# daughterboard.net
KiCad netlist of a schematic drawn in EAGLE
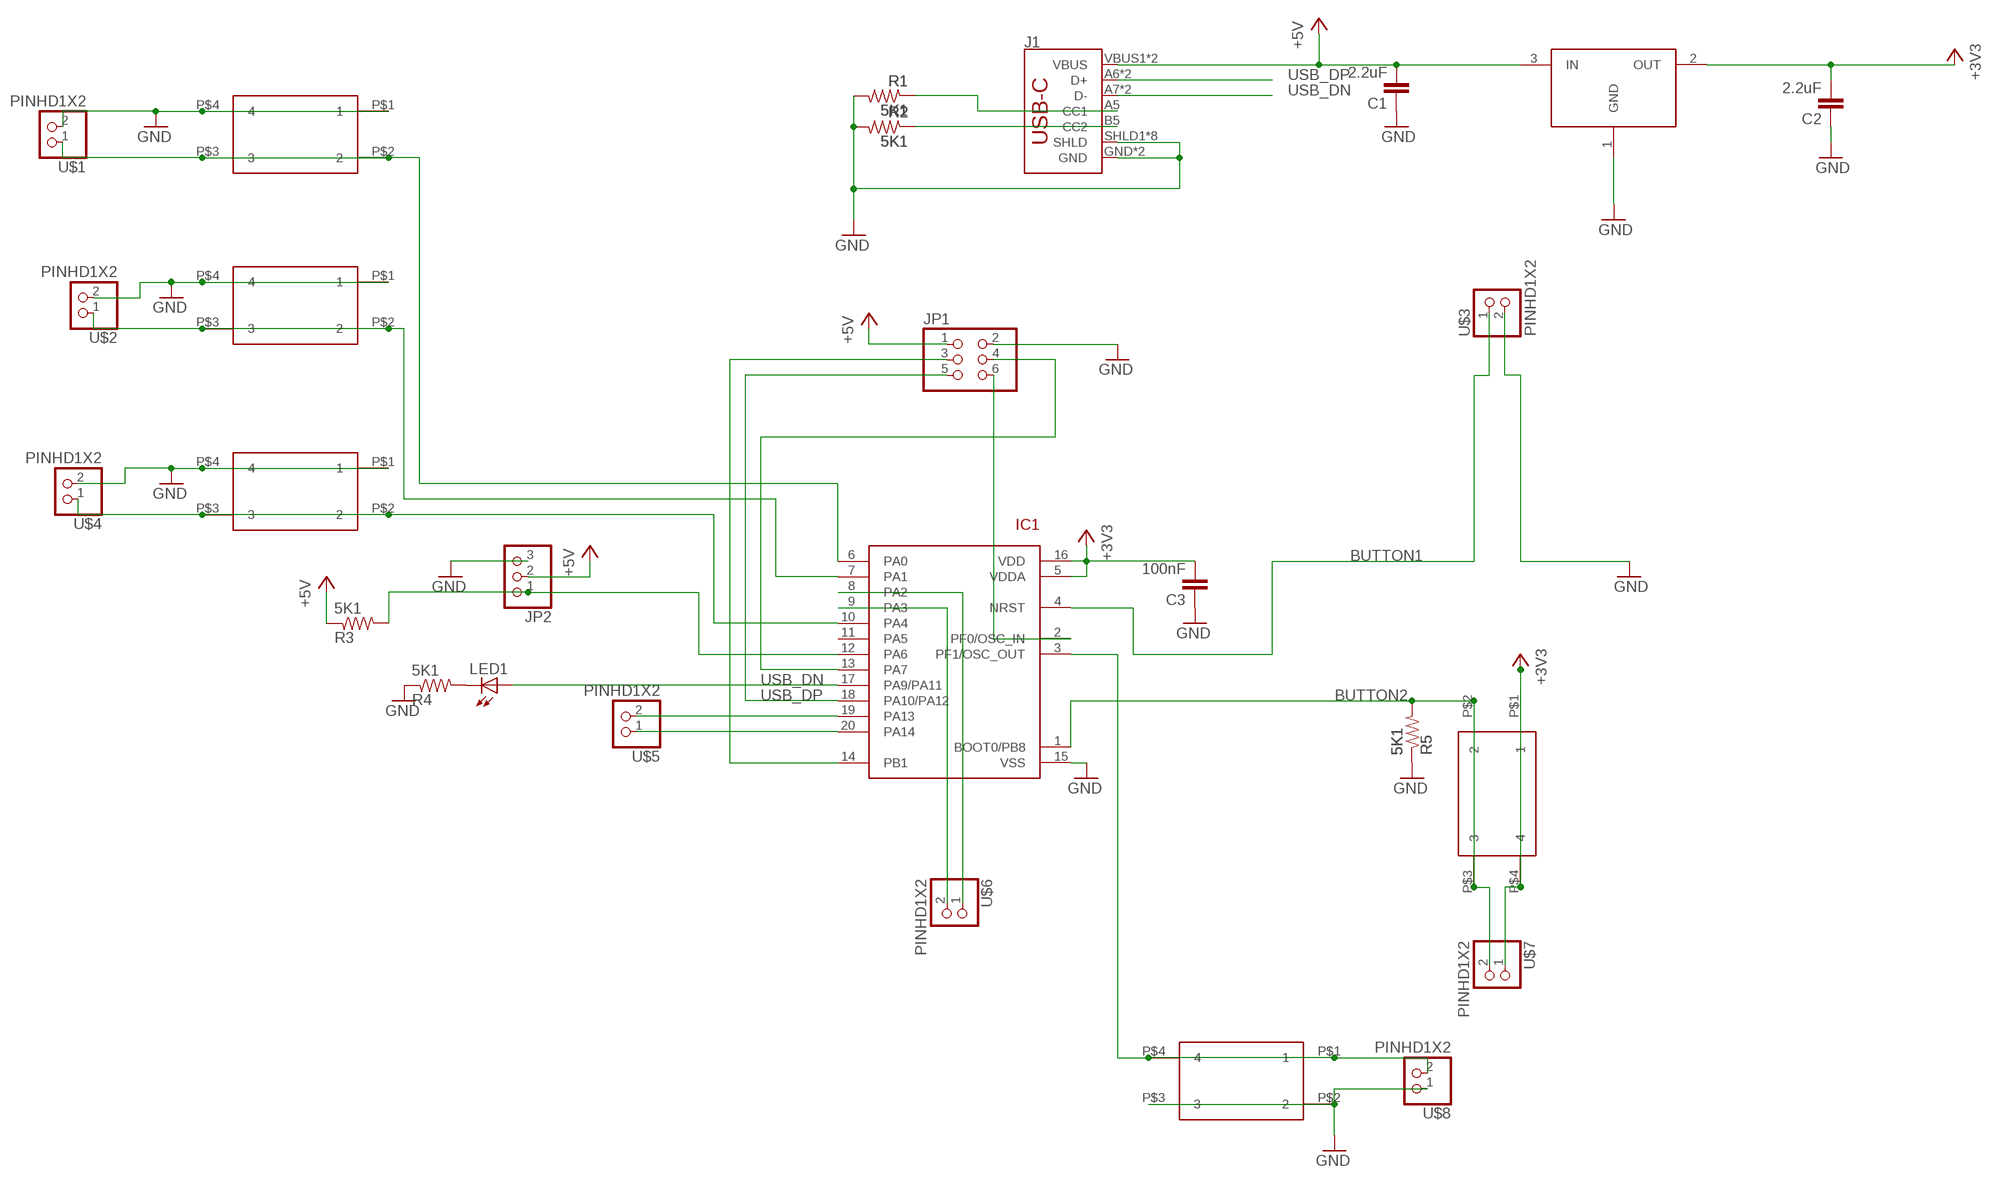
[diagram p0: schematic, sheet 1]

(export (version "E")
  (design (tool "Eeschema 10.0.6"))
  (components
    (comp (ref "C1")
      (value "2.2uF")
      (footprint "eagle-import:0805@1")
      (libsource (lib "eagle-import") (part "CAP0805"))
    )
    (comp (ref "C2")
      (value "2.2uF")
      (footprint "eagle-import:0805@1")
      (libsource (lib "eagle-import") (part "CAP0805"))
    )
    (comp (ref "C3")
      (value "100nF")
      (footprint "eagle-import:0805@1")
      (libsource (lib "eagle-import") (part "CAP0805"))
    )
    (comp (ref "IC1")
      (value "STM32F042F4")
      (footprint "eagle-import:TSSOP20")
      (libsource (lib "eagle-import") (part "STM32F042F4"))
    )
    (comp (ref "J1")
      (value "USB_C16PIN")
      (footprint "eagle-import:USB-C-16P")
      (libsource (lib "eagle-import") (part "USB_C16PIN"))
    )
    (comp (ref "JP1")
      (value "PINHD-2X3")
      (footprint "eagle-import:2X03")
      (libsource (lib "eagle-import") (part "PINHD-2X3"))
    )
    (comp (ref "JP2")
      (value "PINHD-1X3CB")
      (footprint "eagle-import:1X03-CLEANBIG")
      (libsource (lib "eagle-import") (part "PINHD-1X3CB"))
    )
    (comp (ref "LED1")
      (value "LEDCHIP-LED0805")
      (footprint "eagle-import:CHIP-LED0805")
      (libsource (lib "eagle-import") (part "LEDCHIP-LED0805"))
    )
    (comp (ref "R1")
      (value "5K1")
      (footprint "eagle-import:0805")
      (libsource (lib "eagle-import") (part "joyAnalog_RESISTOR0805-RES"))
    )
    (comp (ref "R2")
      (value "5K1")
      (footprint "eagle-import:0805")
      (libsource (lib "eagle-import") (part "joyAnalog_RESISTOR0805-RES"))
    )
    (comp (ref "R3")
      (value "5K1")
      (footprint "eagle-import:0805")
      (libsource (lib "eagle-import") (part "RESISTOR0805-RES"))
    )
    (comp (ref "R4")
      (value "5K1")
      (footprint "eagle-import:0805")
      (libsource (lib "eagle-import") (part "RESISTOR0805-RES"))
    )
    (comp (ref "R5")
      (value "5K1")
      (footprint "eagle-import:0805")
      (libsource (lib "eagle-import") (part "joyAnalog_RESISTOR0805-RES"))
    )
    (comp (ref "SW1")
      (value "324_SW")
      (footprint "eagle-import:342_SWICH_FOOT")
      (libsource (lib "eagle-import") (part "324_SW"))
    )
    (comp (ref "SW2")
      (value "324_SW")
      (footprint "eagle-import:342_SWICH_FOOT")
      (libsource (lib "eagle-import") (part "324_SW"))
    )
    (comp (ref "SW3")
      (value "324_SW")
      (footprint "eagle-import:342_SWICH_FOOT")
      (libsource (lib "eagle-import") (part "324_SW"))
    )
    (comp (ref "SW4")
      (value "324_SW")
      (footprint "eagle-import:342_SWICH_FOOT")
      (libsource (lib "eagle-import") (part "324_SW"))
    )
    (comp (ref "SW5")
      (value "324_SW")
      (footprint "eagle-import:342_SWICH_FOOT")
      (libsource (lib "eagle-import") (part "324_SW"))
    )
    (comp (ref "U$1")
      (value "PINHD1X2")
      (footprint "eagle-import:1X02")
      (libsource (lib "eagle-import") (part "PINHD1X2"))
    )
    (comp (ref "U$2")
      (value "PINHD1X2")
      (footprint "eagle-import:1X02")
      (libsource (lib "eagle-import") (part "PINHD1X2"))
    )
    (comp (ref "U$3")
      (value "PINHD1X2")
      (footprint "eagle-import:1X02")
      (libsource (lib "eagle-import") (part "PINHD1X2"))
    )
    (comp (ref "U$4")
      (value "PINHD1X2")
      (footprint "eagle-import:1X02")
      (libsource (lib "eagle-import") (part "PINHD1X2"))
    )
    (comp (ref "U$5")
      (value "PINHD1X2")
      (footprint "eagle-import:1X02")
      (libsource (lib "eagle-import") (part "PINHD1X2"))
    )
    (comp (ref "U$6")
      (value "PINHD1X2")
      (footprint "eagle-import:1X02")
      (libsource (lib "eagle-import") (part "PINHD1X2"))
    )
    (comp (ref "U$7")
      (value "PINHD1X2")
      (footprint "eagle-import:1X02")
      (libsource (lib "eagle-import") (part "PINHD1X2"))
    )
    (comp (ref "U$8")
      (value "PINHD1X2")
      (footprint "eagle-import:1X02")
      (libsource (lib "eagle-import") (part "PINHD1X2"))
    )
    (comp (ref "U1")
      (value "XC6206_DEV")
      (footprint "eagle-import:SOT23R_INFINEON")
      (libsource (lib "eagle-import") (part "XC6206_DEV"))
    )
  )
  (nets
    (net (code "1") (name "+3V3") (class "Default")
      (node (ref "C2") (pin "2") (pinfunction "2_2") (pintype "passive"))
      (node (ref "C3") (pin "2") (pinfunction "2_2") (pintype "passive"))
      (node (ref "IC1") (pin "16") (pinfunction "VDD_16") (pintype "bidirectional"))
      (node (ref "IC1") (pin "5") (pinfunction "VDDA_5") (pintype "bidirectional"))
      (node (ref "SW4") (pin "P$1") (pinfunction "1_P$1") (pintype "bidirectional"))
      (node (ref "SW4") (pin "P$4") (pinfunction "4_P$4") (pintype "bidirectional"))
      (node (ref "U$7") (pin "1") (pinfunction "1_1") (pintype "passive"))
      (node (ref "U1") (pin "2") (pinfunction "OUT_2") (pintype "bidirectional"))
    )
    (net (code "2") (name "+5V") (class "Default")
      (node (ref "C1") (pin "2") (pinfunction "2_2") (pintype "passive"))
      (node (ref "J1") (pin "VBUS1") (pinfunction "VBUS_VBUS1") (pintype "bidirectional"))
      (node (ref "J1") (pin "VBUS2") (pinfunction "VBUS_VBUS2") (pintype "bidirectional"))
      (node (ref "JP1") (pin "1") (pinfunction "1_1") (pintype "passive"))
      (node (ref "JP2") (pin "2") (pinfunction "2_2") (pintype "passive"))
      (node (ref "R3") (pin "1") (pinfunction "1_1") (pintype "passive"))
      (node (ref "U1") (pin "3") (pinfunction "IN_3") (pintype "bidirectional"))
    )
    (net (code "3") (name "/BUTTON1") (class "Default")
      (node (ref "IC1") (pin "4") (pinfunction "NRST_4") (pintype "bidirectional"))
      (node (ref "U$3") (pin "1") (pinfunction "1_1") (pintype "passive"))
    )
    (net (code "4") (name "/BUTTON2") (class "Default")
      (node (ref "IC1") (pin "1") (pinfunction "BOOT0/PB8_1") (pintype "bidirectional"))
      (node (ref "R5") (pin "2") (pinfunction "2_2") (pintype "passive"))
      (node (ref "SW4") (pin "P$2") (pinfunction "2_P$2") (pintype "bidirectional"))
      (node (ref "SW4") (pin "P$3") (pinfunction "3_P$3") (pintype "bidirectional"))
      (node (ref "U$7") (pin "2") (pinfunction "2_2") (pintype "passive"))
    )
    (net (code "5") (name "/USB_DN") (class "Default")
      (node (ref "IC1") (pin "17") (pinfunction "PA9/PA11_17") (pintype "bidirectional"))
      (node (ref "J1") (pin "A7") (pinfunction "D-_A7") (pintype "bidirectional"))
      (node (ref "J1") (pin "B7") (pinfunction "D-_B7") (pintype "bidirectional"))
      (node (ref "LED1") (pin "A") (pinfunction "A_A") (pintype "passive"))
    )
    (net (code "6") (name "/USB_DP") (class "Default")
      (node (ref "IC1") (pin "18") (pinfunction "PA10/PA12_18") (pintype "bidirectional"))
      (node (ref "J1") (pin "A6") (pinfunction "D+_A6") (pintype "bidirectional"))
      (node (ref "J1") (pin "B6") (pinfunction "D+_B6") (pintype "bidirectional"))
      (node (ref "JP1") (pin "5") (pinfunction "5_5") (pintype "passive"))
    )
    (net (code "7") (name "GND") (class "Default")
      (node (ref "C1") (pin "1") (pinfunction "1_1") (pintype "passive"))
      (node (ref "C2") (pin "1") (pinfunction "1_1") (pintype "passive"))
      (node (ref "C3") (pin "1") (pinfunction "1_1") (pintype "passive"))
      (node (ref "IC1") (pin "15") (pinfunction "VSS_15") (pintype "bidirectional"))
      (node (ref "J1") (pin "GND") (pinfunction "GND_GND") (pintype "bidirectional"))
      (node (ref "J1") (pin "GND2") (pinfunction "GND_GND2") (pintype "bidirectional"))
      (node (ref "J1") (pin "SHLD1") (pinfunction "SHLD_SHLD1") (pintype "bidirectional"))
      (node (ref "J1") (pin "SHLD2") (pinfunction "SHLD_SHLD2") (pintype "bidirectional"))
      (node (ref "J1") (pin "SHLD3") (pinfunction "SHLD_SHLD3") (pintype "bidirectional"))
      (node (ref "J1") (pin "SHLD4") (pinfunction "SHLD_SHLD4") (pintype "bidirectional"))
      (node (ref "J1") (pin "SHLD5") (pinfunction "SHLD_SHLD5") (pintype "bidirectional"))
      (node (ref "J1") (pin "SHLD6") (pinfunction "SHLD_SHLD6") (pintype "bidirectional"))
      (node (ref "J1") (pin "SHLD7") (pinfunction "SHLD_SHLD7") (pintype "bidirectional"))
      (node (ref "J1") (pin "SHLD8") (pinfunction "SHLD_SHLD8") (pintype "bidirectional"))
      (node (ref "JP1") (pin "2") (pinfunction "2_2") (pintype "passive"))
      (node (ref "JP2") (pin "3") (pinfunction "3_3") (pintype "passive"))
      (node (ref "R1") (pin "2") (pinfunction "2_2") (pintype "passive"))
      (node (ref "R2") (pin "2") (pinfunction "2_2") (pintype "passive"))
      (node (ref "R4") (pin "1") (pinfunction "1_1") (pintype "passive"))
      (node (ref "R5") (pin "1") (pinfunction "1_1") (pintype "passive"))
      (node (ref "SW1") (pin "P$1") (pinfunction "1_P$1") (pintype "bidirectional"))
      (node (ref "SW1") (pin "P$4") (pinfunction "4_P$4") (pintype "bidirectional"))
      (node (ref "SW2") (pin "P$1") (pinfunction "1_P$1") (pintype "bidirectional"))
      (node (ref "SW2") (pin "P$4") (pinfunction "4_P$4") (pintype "bidirectional"))
      (node (ref "SW3") (pin "P$1") (pinfunction "1_P$1") (pintype "bidirectional"))
      (node (ref "SW3") (pin "P$4") (pinfunction "4_P$4") (pintype "bidirectional"))
      (node (ref "SW5") (pin "P$2") (pinfunction "2_P$2") (pintype "bidirectional"))
      (node (ref "SW5") (pin "P$3") (pinfunction "3_P$3") (pintype "bidirectional"))
      (node (ref "U$1") (pin "2") (pinfunction "2_2") (pintype "passive"))
      (node (ref "U$2") (pin "2") (pinfunction "2_2") (pintype "passive"))
      (node (ref "U$3") (pin "2") (pinfunction "2_2") (pintype "passive"))
      (node (ref "U$4") (pin "2") (pinfunction "2_2") (pintype "passive"))
      (node (ref "U$8") (pin "1") (pinfunction "1_1") (pintype "passive"))
      (node (ref "U1") (pin "1") (pinfunction "GND_1") (pintype "bidirectional"))
    )
    (net (code "8") (name "Net-(IC1-PA0)") (class "Default")
      (node (ref "IC1") (pin "6") (pinfunction "PA0_6") (pintype "bidirectional"))
      (node (ref "SW1") (pin "P$2") (pinfunction "2_P$2") (pintype "bidirectional"))
      (node (ref "SW1") (pin "P$3") (pinfunction "3_P$3") (pintype "bidirectional"))
      (node (ref "U$1") (pin "1") (pinfunction "1_1") (pintype "passive"))
    )
    (net (code "9") (name "Net-(IC1-PA1)") (class "Default")
      (node (ref "IC1") (pin "7") (pinfunction "PA1_7") (pintype "bidirectional"))
      (node (ref "SW2") (pin "P$2") (pinfunction "2_P$2") (pintype "bidirectional"))
      (node (ref "SW2") (pin "P$3") (pinfunction "3_P$3") (pintype "bidirectional"))
      (node (ref "U$2") (pin "1") (pinfunction "1_1") (pintype "passive"))
    )
    (net (code "10") (name "Net-(IC1-PA2)") (class "Default")
      (node (ref "IC1") (pin "8") (pinfunction "PA2_8") (pintype "bidirectional"))
      (node (ref "U$6") (pin "1") (pinfunction "1_1") (pintype "passive"))
    )
    (net (code "11") (name "Net-(IC1-PA3)") (class "Default")
      (node (ref "IC1") (pin "9") (pinfunction "PA3_9") (pintype "bidirectional"))
      (node (ref "U$6") (pin "2") (pinfunction "2_2") (pintype "passive"))
    )
    (net (code "12") (name "Net-(IC1-PA4)") (class "Default")
      (node (ref "IC1") (pin "10") (pinfunction "PA4_10") (pintype "bidirectional"))
      (node (ref "SW3") (pin "P$2") (pinfunction "2_P$2") (pintype "bidirectional"))
      (node (ref "SW3") (pin "P$3") (pinfunction "3_P$3") (pintype "bidirectional"))
      (node (ref "U$4") (pin "1") (pinfunction "1_1") (pintype "passive"))
    )
    (net (code "13") (name "Net-(IC1-PA6)") (class "Default")
      (node (ref "IC1") (pin "12") (pinfunction "PA6_12") (pintype "bidirectional"))
      (node (ref "JP2") (pin "1") (pinfunction "1_1") (pintype "passive"))
      (node (ref "R3") (pin "2") (pinfunction "2_2") (pintype "passive"))
    )
    (net (code "14") (name "Net-(IC1-PA7)") (class "Default")
      (node (ref "IC1") (pin "13") (pinfunction "PA7_13") (pintype "bidirectional"))
      (node (ref "JP1") (pin "4") (pinfunction "4_4") (pintype "passive"))
    )
    (net (code "15") (name "Net-(IC1-PA13)") (class "Default")
      (node (ref "IC1") (pin "19") (pinfunction "PA13_19") (pintype "bidirectional"))
      (node (ref "U$5") (pin "2") (pinfunction "2_2") (pintype "passive"))
    )
    (net (code "16") (name "Net-(IC1-PA14)") (class "Default")
      (node (ref "IC1") (pin "20") (pinfunction "PA14_20") (pintype "bidirectional"))
      (node (ref "U$5") (pin "1") (pinfunction "1_1") (pintype "passive"))
    )
    (net (code "17") (name "Net-(IC1-PB1)") (class "Default")
      (node (ref "IC1") (pin "14") (pinfunction "PB1_14") (pintype "bidirectional"))
      (node (ref "JP1") (pin "3") (pinfunction "3_3") (pintype "passive"))
    )
    (net (code "18") (name "Net-(IC1-PF0{slash}OSC_IN)") (class "Default")
      (node (ref "IC1") (pin "2") (pinfunction "PF0/OSC_IN_2") (pintype "bidirectional"))
      (node (ref "JP1") (pin "6") (pinfunction "6_6") (pintype "passive"))
    )
    (net (code "19") (name "Net-(IC1-PF1{slash}OSC_OUT)") (class "Default")
      (node (ref "IC1") (pin "3") (pinfunction "PF1/OSC_OUT_3") (pintype "bidirectional"))
      (node (ref "SW5") (pin "P$1") (pinfunction "1_P$1") (pintype "bidirectional"))
      (node (ref "SW5") (pin "P$4") (pinfunction "4_P$4") (pintype "bidirectional"))
      (node (ref "U$8") (pin "2") (pinfunction "2_2") (pintype "passive"))
    )
    (net (code "20") (name "Net-(J1-CC1)") (class "Default")
      (node (ref "J1") (pin "A5") (pinfunction "CC1_A5") (pintype "bidirectional"))
      (node (ref "R1") (pin "1") (pinfunction "1_1") (pintype "passive"))
    )
    (net (code "21") (name "Net-(J1-CC2)") (class "Default")
      (node (ref "J1") (pin "B5") (pinfunction "CC2_B5") (pintype "bidirectional"))
      (node (ref "R2") (pin "1") (pinfunction "1_1") (pintype "passive"))
    )
    (net (code "22") (name "Net-(LED1-PadC)") (class "Default")
      (node (ref "LED1") (pin "C") (pinfunction "C_C") (pintype "passive"))
      (node (ref "R4") (pin "2") (pinfunction "2_2") (pintype "passive"))
    )
    (net (code "23") (name "unconnected-(IC1-PA5-Pad11)") (class "Default")
      (node (ref "IC1") (pin "11") (pinfunction "PA5_11") (pintype "bidirectional"))
    )
  )
)
